# Power.net
KiCad netlist of a schematic drawn in Altium Designer
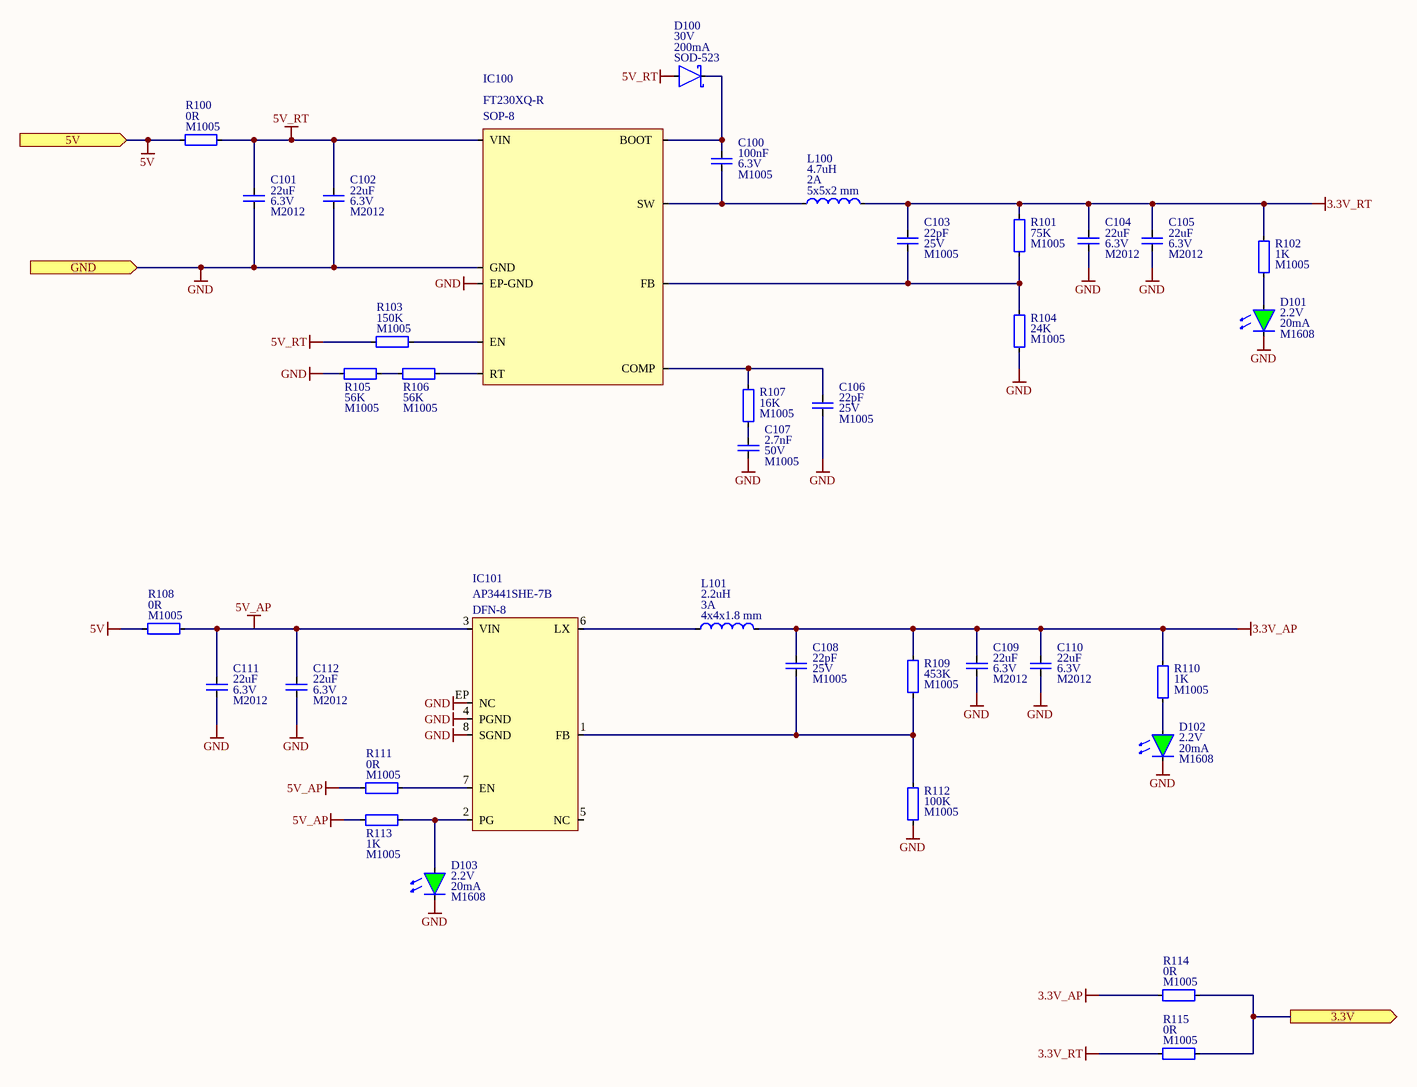
[diagram p0: Power.SchDoc]

(export (version "E")
  (design (tool "Eeschema 10.0.6"))
  (components
    (comp (ref "C100")
      (value "100nF")
      (footprint "Capacitor_Ceramic_M1005_I0402")
      (description "Cap, Cer, 100nF, 6.3V, M1005")
      (fields
        (field (name "VOLTAGE") "6.3V")
        (field (name "MANUFACTURER PART NUMBER") "04026D104KAT4A")
        (field (name "MANUFACTURER") "Kyocera")
        (field (name "PACKAGE") "M1005")
      )
      (libsource (lib "Capacitor") (part "Capacitor_Ceramic"))
    )
    (comp (ref "C101")
      (value "22uF")
      (footprint "Capacitor_Ceramic_M2012_I0805")
      (description "Cap, Cer, 22uF, 6.3V, M2012")
      (fields
        (field (name "VOLTAGE") "6.3V")
        (field (name "MANUFACTURER PART NUMBER") "GRM21BR60J226ME39K")
        (field (name "MANUFACTURER") "Murata")
        (field (name "PACKAGE") "M2012")
      )
      (libsource (lib "Capacitor") (part "Capacitor_Ceramic"))
    )
    (comp (ref "C102")
      (value "22uF")
      (footprint "Capacitor_Ceramic_M2012_I0805")
      (description "Cap, Cer, 22uF, 6.3V, M2012")
      (fields
        (field (name "VOLTAGE") "6.3V")
        (field (name "MANUFACTURER PART NUMBER") "GRM21BR60J226ME39K")
        (field (name "MANUFACTURER") "Murata")
        (field (name "PACKAGE") "M2012")
      )
      (libsource (lib "Capacitor") (part "Capacitor_Ceramic"))
    )
    (comp (ref "C103")
      (value "22pF")
      (footprint "Capacitor_Ceramic_M1005_I0402")
      (description "Cap, Cer, 22pF, 25V, M1005")
      (fields
        (field (name "VOLTAGE") "25V")
        (field (name "MANUFACTURER PART NUMBER") "0402N220J250CT")
        (field (name "MANUFACTURER") "Walsin")
        (field (name "PACKAGE") "M1005")
      )
      (libsource (lib "Capacitor") (part "Capacitor_Ceramic"))
    )
    (comp (ref "C104")
      (value "22uF")
      (footprint "Capacitor_Ceramic_M2012_I0805")
      (description "Cap, Cer, 22uF, 6.3V, M2012")
      (fields
        (field (name "VOLTAGE") "6.3V")
        (field (name "MANUFACTURER PART NUMBER") "GRM21BR60J226ME39K")
        (field (name "MANUFACTURER") "Murata")
        (field (name "PACKAGE") "M2012")
      )
      (libsource (lib "Capacitor") (part "Capacitor_Ceramic"))
    )
    (comp (ref "C105")
      (value "22uF")
      (footprint "Capacitor_Ceramic_M2012_I0805")
      (description "Cap, Cer, 22uF, 6.3V, M2012")
      (fields
        (field (name "VOLTAGE") "6.3V")
        (field (name "MANUFACTURER PART NUMBER") "GRM21BR60J226ME39K")
        (field (name "MANUFACTURER") "Murata")
        (field (name "PACKAGE") "M2012")
      )
      (libsource (lib "Capacitor") (part "Capacitor_Ceramic"))
    )
    (comp (ref "C106")
      (value "22pF")
      (footprint "Capacitor_Ceramic_M1005_I0402")
      (description "Cap, Cer, 22pF, 25V, M1005")
      (fields
        (field (name "VOLTAGE") "25V")
        (field (name "MANUFACTURER PART NUMBER") "0402N220J250CT")
        (field (name "MANUFACTURER") "Walsin")
        (field (name "PACKAGE") "M1005")
      )
      (libsource (lib "Capacitor") (part "Capacitor_Ceramic"))
    )
    (comp (ref "C107")
      (value "2.7nF")
      (footprint "Capacitor_Ceramic_M1005_I0402")
      (description "Cap, Cer, 2.7nF, 50V, M1005")
      (fields
        (field (name "VOLTAGE") "50V")
        (field (name "MANUFACTURER PART NUMBER") "CC0402KRX7R9BB272")
        (field (name "MANUFACTURER") "Yageo")
        (field (name "PACKAGE") "M1005")
      )
      (libsource (lib "Capacitor") (part "Capacitor_Ceramic"))
    )
    (comp (ref "C108")
      (value "22pF")
      (footprint "Capacitor_Ceramic_M1005_I0402")
      (description "Cap, Cer, 22pF, 25V, M1005")
      (fields
        (field (name "VOLTAGE") "25V")
        (field (name "MANUFACTURER PART NUMBER") "0402N220J250CT")
        (field (name "MANUFACTURER") "Walsin")
        (field (name "PACKAGE") "M1005")
      )
      (libsource (lib "Capacitor") (part "Capacitor_Ceramic"))
    )
    (comp (ref "C109")
      (value "22uF")
      (footprint "Capacitor_Ceramic_M2012_I0805")
      (description "Cap, Cer, 22uF, 6.3V, M2012")
      (fields
        (field (name "VOLTAGE") "6.3V")
        (field (name "MANUFACTURER PART NUMBER") "GRM21BR60J226ME39K")
        (field (name "MANUFACTURER") "Murata")
        (field (name "PACKAGE") "M2012")
      )
      (libsource (lib "Capacitor") (part "Capacitor_Ceramic"))
    )
    (comp (ref "C110")
      (value "22uF")
      (footprint "Capacitor_Ceramic_M2012_I0805")
      (description "Cap, Cer, 22uF, 6.3V, M2012")
      (fields
        (field (name "VOLTAGE") "6.3V")
        (field (name "MANUFACTURER PART NUMBER") "GRM21BR60J226ME39K")
        (field (name "MANUFACTURER") "Murata")
        (field (name "PACKAGE") "M2012")
      )
      (libsource (lib "Capacitor") (part "Capacitor_Ceramic"))
    )
    (comp (ref "C111")
      (value "22uF")
      (footprint "Capacitor_Ceramic_M2012_I0805")
      (description "Cap, Cer, 22uF, 6.3V, M2012")
      (fields
        (field (name "VOLTAGE") "6.3V")
        (field (name "MANUFACTURER PART NUMBER") "GRM21BR60J226ME39K")
        (field (name "MANUFACTURER") "Murata")
        (field (name "PACKAGE") "M2012")
      )
      (libsource (lib "Capacitor") (part "Capacitor_Ceramic"))
    )
    (comp (ref "C112")
      (value "22uF")
      (footprint "Capacitor_Ceramic_M2012_I0805")
      (description "Cap, Cer, 22uF, 6.3V, M2012")
      (fields
        (field (name "VOLTAGE") "6.3V")
        (field (name "MANUFACTURER PART NUMBER") "GRM21BR60J226ME39K")
        (field (name "MANUFACTURER") "Murata")
        (field (name "PACKAGE") "M2012")
      )
      (libsource (lib "Capacitor") (part "Capacitor_Ceramic"))
    )
    (comp (ref "D100")
      (value "Diode_Schottky")
      (footprint "Diode_SOD-523_SC-79")
      (description "Diode, Schottky, 30V, 200mA, SOD-523")
      (fields
        (field (name "MANUFACTURER PART NUMBER") "CES521,L3F")
        (field (name "MANUFACTURER") "Toshiba")
        (field (name "CURRENT") "200mA")
        (field (name "VOLTAGE") "30V")
        (field (name "PACKAGE") "SOD-523")
      )
      (libsource (lib "Diode") (part "Diode_Schottky"))
    )
    (comp (ref "D101")
      (value "Diode_Led")
      (footprint "Diode_Smd_M1608_I0603_Green-Yellow")
      (description "Diode, Led, Green-Yellow, 2.2V, 20mA, M1608")
      (fields
        (field (name "MANUFACTURER PART NUMBER") "SML-D12M1WT86")
        (field (name "MANUFACTURER") "Rohm")
        (field (name "CURRENT") "20mA")
        (field (name "VOLTAGE") "2.2V")
        (field (name "PACKAGE") "M1608")
      )
      (libsource (lib "Diode") (part "Diode_Led"))
    )
    (comp (ref "D102")
      (value "Diode_Led")
      (footprint "Diode_Smd_M1608_I0603_Green-Yellow")
      (description "Diode, Led, Green-Yellow, 2.2V, 20mA, M1608")
      (fields
        (field (name "MANUFACTURER PART NUMBER") "SML-D12M1WT86")
        (field (name "MANUFACTURER") "Rohm")
        (field (name "CURRENT") "20mA")
        (field (name "VOLTAGE") "2.2V")
        (field (name "PACKAGE") "M1608")
      )
      (libsource (lib "Diode") (part "Diode_Led"))
    )
    (comp (ref "D103")
      (value "Diode_Led")
      (footprint "Diode_Smd_M1608_I0603_Green-Yellow")
      (description "Diode, Led, Green-Yellow, 2.2V, 20mA, M1608")
      (fields
        (field (name "MANUFACTURER PART NUMBER") "SML-D12M1WT86")
        (field (name "MANUFACTURER") "Rohm")
        (field (name "CURRENT") "20mA")
        (field (name "VOLTAGE") "2.2V")
        (field (name "PACKAGE") "M1608")
      )
      (libsource (lib "Diode") (part "Diode_Led"))
    )
    (comp (ref "IC100")
      (value "Richtek, RT2862xSP")
      (footprint "Richtek, RT2862xSP,SOP-8")
      (description "IC,Interface,FTDI,QFN16")
      (fields
        (field (name "MANUFACTURER") "FTDI")
        (field (name "MANUFACTURER PART NUMBER") "FT230XQ-R")
        (field (name "PACKAGE") "SOP-8")
      )
      (libsource (lib "IC-Power-DC-DC") (part "Richtek, RT2862xSP"))
    )
    (comp (ref "IC101")
      (value "Diodes, AP3441")
      (footprint "DFN-8, 2mm x 2mm, 0.5mm")
      (description "IC, Power, Buck, DFN-8, 2x2")
      (fields
        (field (name "MANUFACTURER") "Richtek")
        (field (name "MANUFACTURER PART NUMBER") "AP3441SHE-7B")
        (field (name "PACKAGE") "DFN-8")
      )
      (libsource (lib "IC-Power-DC-DC") (part "Diodes, AP3441"))
    )
    (comp (ref "L100")
      (value "4.7uH")
      (footprint "Taiyo Yuden - Power Inductor, 5050WK")
      (description "Inductor, Power, 4.7uH, 2A, 5x5x2mm")
      (fields
        (field (name "MANUFACTURER PART NUMBER") "NRS5020T4R7MMGJ")
        (field (name "MANUFACTURER") "Taiyo Yuden")
        (field (name "SATURATION CURRENT") "2A")
        (field (name "PACKAGE") "5x5x2 mm")
      )
      (libsource (lib "Inductor") (part "Inductor"))
    )
    (comp (ref "L101")
      (value "2.2uH")
      (footprint "Taiyo Yuden - Power Inductor, 4040TK")
      (description "Inductor, Power, 2.2uH, 3A, 4x4x1.8mm")
      (fields
        (field (name "MANUFACTURER PART NUMBER") "NRS4018T2R2MDGJ")
        (field (name "MANUFACTURER") "Taiyo Yuden")
        (field (name "SATURATION CURRENT") "3A")
        (field (name "PACKAGE") "4x4x1.8 mm")
      )
      (libsource (lib "Inductor") (part "Inductor"))
    )
    (comp (ref "R100")
      (value "0R")
      (footprint "Resistor_Smd_M1005_I0402")
      (description "Res, 0R, M1005")
      (fields
        (field (name "MANUFACTURER") "Yageo")
        (field (name "MANUFACTURER PART NUMBER") "RC0402FR-070RL")
        (field (name "PACKAGE") "M1005")
      )
      (libsource (lib "Resistor") (part "Resistor"))
    )
    (comp (ref "R101")
      (value "75K")
      (footprint "Resistor_Smd_M1005_I0402")
      (description "Res, 75K, 1%, M1005")
      (fields
        (field (name "TOLERANCE") "1%")
        (field (name "MANUFACTURER") "Yageo")
        (field (name "PACKAGE") "M1005")
      )
      (libsource (lib "Resistor") (part "Resistor"))
    )
    (comp (ref "R102")
      (value "1K")
      (footprint "Resistor_Smd_M1005_I0402")
      (description "Res, 1K, 1%, M1005")
      (fields
        (field (name "TOLERANCE") "1%")
        (field (name "MANUFACTURER") "Yageo")
        (field (name "PACKAGE") "M1005")
      )
      (libsource (lib "Resistor") (part "Resistor"))
    )
    (comp (ref "R103")
      (value "150K")
      (footprint "Resistor_Smd_M1005_I0402")
      (description "Res, 150K, 1%, M1005")
      (fields
        (field (name "TOLERANCE") "1%")
        (field (name "MANUFACTURER") "Yageo")
        (field (name "PACKAGE") "M1005")
      )
      (libsource (lib "Resistor") (part "Resistor"))
    )
    (comp (ref "R104")
      (value "24K")
      (footprint "Resistor_Smd_M1005_I0402")
      (description "Res, 24K, 1%, M1005")
      (fields
        (field (name "TOLERANCE") "1%")
        (field (name "MANUFACTURER") "Yageo")
        (field (name "PACKAGE") "M1005")
      )
      (libsource (lib "Resistor") (part "Resistor"))
    )
    (comp (ref "R105")
      (value "56K")
      (footprint "Resistor_Smd_M1005_I0402")
      (description "Res, 56K, 1%, M1005")
      (fields
        (field (name "TOLERANCE") "1%")
        (field (name "MANUFACTURER") "Yageo")
        (field (name "PACKAGE") "M1005")
      )
      (libsource (lib "Resistor") (part "Resistor"))
    )
    (comp (ref "R106")
      (value "56K")
      (footprint "Resistor_Smd_M1005_I0402")
      (description "Res, 56K, 1%, M1005")
      (fields
        (field (name "TOLERANCE") "1%")
        (field (name "MANUFACTURER") "Yageo")
        (field (name "PACKAGE") "M1005")
      )
      (libsource (lib "Resistor") (part "Resistor"))
    )
    (comp (ref "R107")
      (value "16K")
      (footprint "Resistor_Smd_M1005_I0402")
      (description "Res, 16K, 1%, M1005")
      (fields
        (field (name "TOLERANCE") "1%")
        (field (name "MANUFACTURER") "Yageo")
        (field (name "PACKAGE") "M1005")
      )
      (libsource (lib "Resistor") (part "Resistor"))
    )
    (comp (ref "R108")
      (value "0R")
      (footprint "Resistor_Smd_M1005_I0402")
      (description "Res, 0R, M1005")
      (fields
        (field (name "MANUFACTURER") "Yageo")
        (field (name "MANUFACTURER PART NUMBER") "RC0402FR-070RL")
        (field (name "PACKAGE") "M1005")
      )
      (libsource (lib "Resistor") (part "Resistor"))
    )
    (comp (ref "R109")
      (value "453K")
      (footprint "Resistor_Smd_M1005_I0402")
      (description "Res, 453K, 1%, M1005")
      (fields
        (field (name "TOLERANCE") "1%")
        (field (name "MANUFACTURER") "Yageo")
        (field (name "PACKAGE") "M1005")
      )
      (libsource (lib "Resistor") (part "Resistor"))
    )
    (comp (ref "R110")
      (value "1K")
      (footprint "Resistor_Smd_M1005_I0402")
      (description "Res, 1K, 1%, M1005")
      (fields
        (field (name "TOLERANCE") "1%")
        (field (name "MANUFACTURER") "Yageo")
        (field (name "PACKAGE") "M1005")
      )
      (libsource (lib "Resistor") (part "Resistor"))
    )
    (comp (ref "R111")
      (value "0R")
      (footprint "Resistor_Smd_M1005_I0402")
      (description "Res, 0R, M1005")
      (fields
        (field (name "MANUFACTURER") "Yageo")
        (field (name "MANUFACTURER PART NUMBER") "RC0402FR-070RL")
        (field (name "PACKAGE") "M1005")
      )
      (libsource (lib "Resistor") (part "Resistor"))
    )
    (comp (ref "R112")
      (value "100K")
      (footprint "Resistor_Smd_M1005_I0402")
      (description "Res, 100K, 1%, M1005")
      (fields
        (field (name "TOLERANCE") "1%")
        (field (name "MANUFACTURER") "Yageo")
        (field (name "PACKAGE") "M1005")
      )
      (libsource (lib "Resistor") (part "Resistor"))
    )
    (comp (ref "R113")
      (value "1K")
      (footprint "Resistor_Smd_M1005_I0402")
      (description "Res, 1K, 1%, M1005")
      (fields
        (field (name "TOLERANCE") "1%")
        (field (name "MANUFACTURER") "Yageo")
        (field (name "PACKAGE") "M1005")
      )
      (libsource (lib "Resistor") (part "Resistor"))
    )
    (comp (ref "R114")
      (value "0R")
      (footprint "Resistor_Smd_M1005_I0402")
      (description "Res, 0R, M1005")
      (fields
        (field (name "MANUFACTURER") "Yageo")
        (field (name "MANUFACTURER PART NUMBER") "RC0402FR-070RL")
        (field (name "PACKAGE") "M1005")
      )
      (libsource (lib "Resistor") (part "Resistor"))
    )
    (comp (ref "R115")
      (value "0R")
      (footprint "Resistor_Smd_M1005_I0402")
      (description "Res, 0R, M1005")
      (fields
        (field (name "MANUFACTURER") "Yageo")
        (field (name "MANUFACTURER PART NUMBER") "RC0402FR-070RL")
        (field (name "PACKAGE") "M1005")
      )
      (libsource (lib "Resistor") (part "Resistor"))
    )
  )
  (nets
    (net (code "1") (name "/3.3V") (class "Default")
      (node (ref "R114") (pin "2") (pinfunction "2_2") (pintype "passive"))
      (node (ref "R115") (pin "2") (pinfunction "2_2") (pintype "passive"))
    )
    (net (code "2") (name "3.3V_AP") (class "Default")
      (node (ref "C108") (pin "1") (pinfunction "1_1") (pintype "passive"))
      (node (ref "C109") (pin "1") (pinfunction "1_1") (pintype "passive"))
      (node (ref "C110") (pin "1") (pinfunction "1_1") (pintype "passive"))
      (node (ref "L101") (pin "2") (pinfunction "2_2") (pintype "passive"))
      (node (ref "R109") (pin "1") (pinfunction "1_1") (pintype "passive"))
      (node (ref "R110") (pin "1") (pinfunction "1_1") (pintype "passive"))
      (node (ref "R114") (pin "1") (pinfunction "1_1") (pintype "passive"))
    )
    (net (code "3") (name "3.3V_RT") (class "Default")
      (node (ref "C103") (pin "1") (pinfunction "1_1") (pintype "passive"))
      (node (ref "C104") (pin "1") (pinfunction "1_1") (pintype "passive"))
      (node (ref "C105") (pin "1") (pinfunction "1_1") (pintype "passive"))
      (node (ref "L100") (pin "2") (pinfunction "2_2") (pintype "passive"))
      (node (ref "R101") (pin "1") (pinfunction "1_1") (pintype "passive"))
      (node (ref "R102") (pin "1") (pinfunction "1_1") (pintype "passive"))
      (node (ref "R115") (pin "1") (pinfunction "1_1") (pintype "passive"))
    )
    (net (code "4") (name "5V") (class "Default")
      (node (ref "R100") (pin "1") (pinfunction "1_1") (pintype "passive"))
      (node (ref "R108") (pin "1") (pinfunction "1_1") (pintype "passive"))
    )
    (net (code "5") (name "5V_AP") (class "Default")
      (node (ref "C111") (pin "1") (pinfunction "1_1") (pintype "passive"))
      (node (ref "C112") (pin "1") (pinfunction "1_1") (pintype "passive"))
      (node (ref "IC101") (pin "3") (pinfunction "VIN_3") (pintype "passive"))
      (node (ref "R108") (pin "2") (pinfunction "2_2") (pintype "passive"))
      (node (ref "R111") (pin "1") (pinfunction "1_1") (pintype "passive"))
      (node (ref "R113") (pin "1") (pinfunction "1_1") (pintype "passive"))
    )
    (net (code "6") (name "5V_RT") (class "Default")
      (node (ref "C101") (pin "1") (pinfunction "1_1") (pintype "passive"))
      (node (ref "C102") (pin "1") (pinfunction "1_1") (pintype "passive"))
      (node (ref "D100") (pin "A") (pinfunction "A_A") (pintype "passive"))
      (node (ref "IC100") (pin "8-VIN") (pinfunction "VIN_8-VIN") (pintype "passive"))
      (node (ref "R100") (pin "2") (pinfunction "2_2") (pintype "passive"))
      (node (ref "R103") (pin "1") (pinfunction "1_1") (pintype "passive"))
    )
    (net (code "7") (name "GND") (class "Default")
      (node (ref "C101") (pin "2") (pinfunction "2_2") (pintype "passive"))
      (node (ref "C102") (pin "2") (pinfunction "2_2") (pintype "passive"))
      (node (ref "C104") (pin "2") (pinfunction "2_2") (pintype "passive"))
      (node (ref "C105") (pin "2") (pinfunction "2_2") (pintype "passive"))
      (node (ref "C106") (pin "2") (pinfunction "2_2") (pintype "passive"))
      (node (ref "C107") (pin "2") (pinfunction "2_2") (pintype "passive"))
      (node (ref "C109") (pin "2") (pinfunction "2_2") (pintype "passive"))
      (node (ref "C110") (pin "2") (pinfunction "2_2") (pintype "passive"))
      (node (ref "C111") (pin "2") (pinfunction "2_2") (pintype "passive"))
      (node (ref "C112") (pin "2") (pinfunction "2_2") (pintype "passive"))
      (node (ref "D101") (pin "C") (pinfunction "C_C") (pintype "passive"))
      (node (ref "D102") (pin "C") (pinfunction "C_C") (pintype "passive"))
      (node (ref "D103") (pin "C") (pinfunction "C_C") (pintype "passive"))
      (node (ref "IC100") (pin "4-GND") (pinfunction "GND_4-GND") (pintype "passive"))
      (node (ref "IC100") (pin "EP-GND") (pinfunction "EP-GND_EP-GND") (pintype "passive"))
      (node (ref "IC101") (pin "4") (pinfunction "PGND_4") (pintype "passive"))
      (node (ref "IC101") (pin "8") (pinfunction "SGND_8") (pintype "passive"))
      (node (ref "IC101") (pin "EP") (pinfunction "NC_EP") (pintype "passive"))
      (node (ref "R104") (pin "2") (pinfunction "2_2") (pintype "passive"))
      (node (ref "R105") (pin "2") (pinfunction "2_2") (pintype "passive"))
      (node (ref "R112") (pin "2") (pinfunction "2_2") (pintype "passive"))
    )
    (net (code "8") (name "Net-(C107-Pad1)") (class "Default")
      (node (ref "C107") (pin "1") (pinfunction "1_1") (pintype "passive"))
      (node (ref "R107") (pin "2") (pinfunction "2_2") (pintype "passive"))
    )
    (net (code "9") (name "Net-(D101-PadA)") (class "Default")
      (node (ref "D101") (pin "A") (pinfunction "A_A") (pintype "passive"))
      (node (ref "R102") (pin "2") (pinfunction "2_2") (pintype "passive"))
    )
    (net (code "10") (name "Net-(D102-PadA)") (class "Default")
      (node (ref "D102") (pin "A") (pinfunction "A_A") (pintype "passive"))
      (node (ref "R110") (pin "2") (pinfunction "2_2") (pintype "passive"))
    )
    (net (code "11") (name "Net-(IC100-BOOT)") (class "Default")
      (node (ref "C100") (pin "1") (pinfunction "1_1") (pintype "passive"))
      (node (ref "D100") (pin "C") (pinfunction "C_C") (pintype "passive"))
      (node (ref "IC100") (pin "2-BOOT") (pinfunction "BOOT_2-BOOT") (pintype "passive"))
    )
    (net (code "12") (name "Net-(IC100-COMP)") (class "Default")
      (node (ref "C106") (pin "1") (pinfunction "1_1") (pintype "passive"))
      (node (ref "IC100") (pin "6-COMP") (pinfunction "COMP_6-COMP") (pintype "passive"))
      (node (ref "R107") (pin "1") (pinfunction "1_1") (pintype "passive"))
    )
    (net (code "13") (name "Net-(IC100-EN)") (class "Default")
      (node (ref "IC100") (pin "3-EN") (pinfunction "EN_3-EN") (pintype "passive"))
      (node (ref "R103") (pin "2") (pinfunction "2_2") (pintype "passive"))
    )
    (net (code "14") (name "Net-(IC100-FB)") (class "Default")
      (node (ref "C103") (pin "2") (pinfunction "2_2") (pintype "passive"))
      (node (ref "IC100") (pin "5-FB") (pinfunction "FB_5-FB") (pintype "passive"))
      (node (ref "R101") (pin "2") (pinfunction "2_2") (pintype "passive"))
      (node (ref "R104") (pin "1") (pinfunction "1_1") (pintype "passive"))
    )
    (net (code "15") (name "Net-(IC100-RT)") (class "Default")
      (node (ref "IC100") (pin "7-RT") (pinfunction "RT_7-RT") (pintype "passive"))
      (node (ref "R106") (pin "1") (pinfunction "1_1") (pintype "passive"))
    )
    (net (code "16") (name "Net-(IC100-SW)") (class "Default")
      (node (ref "C100") (pin "2") (pinfunction "2_2") (pintype "passive"))
      (node (ref "IC100") (pin "1-SW") (pinfunction "SW_1-SW") (pintype "passive"))
      (node (ref "L100") (pin "1") (pinfunction "1_1") (pintype "passive"))
    )
    (net (code "17") (name "Net-(IC101-EN)") (class "Default")
      (node (ref "IC101") (pin "7") (pinfunction "EN_7") (pintype "passive"))
      (node (ref "R111") (pin "2") (pinfunction "2_2") (pintype "passive"))
    )
    (net (code "18") (name "Net-(IC101-FB)") (class "Default")
      (node (ref "C108") (pin "2") (pinfunction "2_2") (pintype "passive"))
      (node (ref "IC101") (pin "1") (pinfunction "FB_1") (pintype "passive"))
      (node (ref "R109") (pin "2") (pinfunction "2_2") (pintype "passive"))
      (node (ref "R112") (pin "1") (pinfunction "1_1") (pintype "passive"))
    )
    (net (code "19") (name "Net-(IC101-LX)") (class "Default")
      (node (ref "IC101") (pin "6") (pinfunction "LX_6") (pintype "passive"))
      (node (ref "L101") (pin "1") (pinfunction "1_1") (pintype "passive"))
    )
    (net (code "20") (name "Net-(IC101-PG)") (class "Default")
      (node (ref "D103") (pin "A") (pinfunction "A_A") (pintype "passive"))
      (node (ref "IC101") (pin "2") (pinfunction "PG_2") (pintype "passive"))
      (node (ref "R113") (pin "2") (pinfunction "2_2") (pintype "passive"))
    )
    (net (code "21") (name "Net-(R105-Pad1)") (class "Default")
      (node (ref "R105") (pin "1") (pinfunction "1_1") (pintype "passive"))
      (node (ref "R106") (pin "2") (pinfunction "2_2") (pintype "passive"))
    )
    (net (code "22") (name "unconnected-(IC101-NC-Pad5)") (class "Default")
      (node (ref "IC101") (pin "5") (pinfunction "NC_5") (pintype "passive"))
    )
  )
)
